# Sheet1.net
KiCad netlist of a schematic drawn in Altium Designer
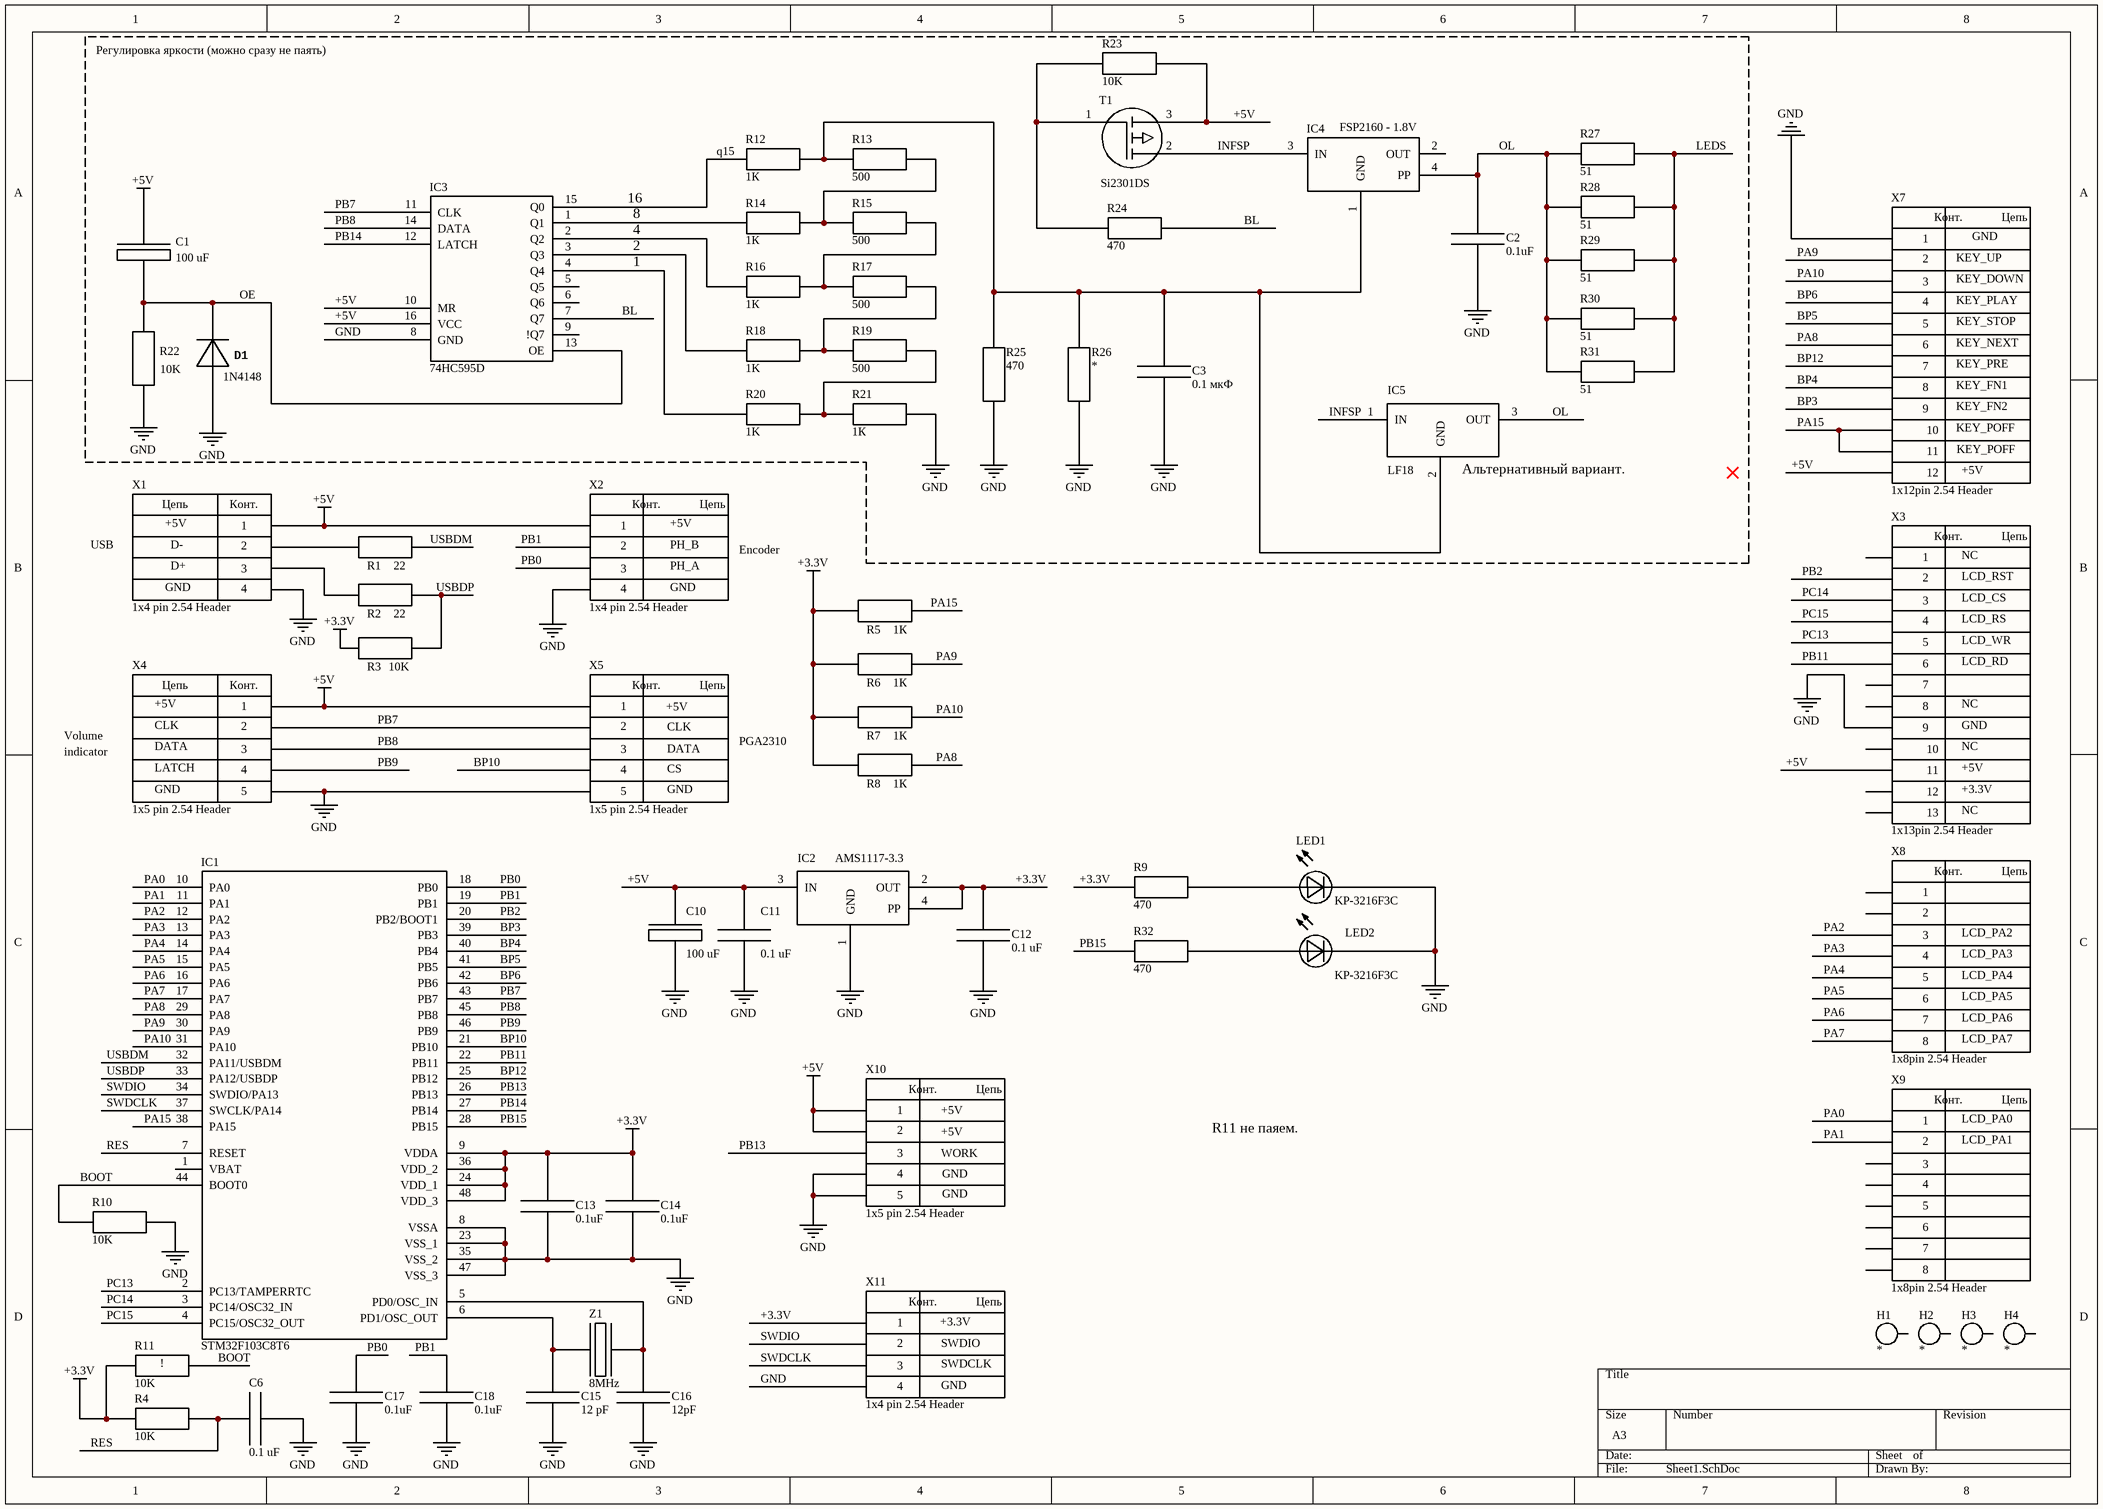
[diagram p0: Sheet1.SchDoc]

(export (version "E")
  (design (tool "Eeschema 10.0.6"))
  (components
    (comp (ref "C1")
      (value "100 uF")
      (footprint "Конденсатор тантал 4x7")
      (description "Танталовый")
      (libsource (lib "") (part "Конденсатор_1"))
    )
    (comp (ref "C2")
      (value "0.1uF")
      (footprint "SMD 1206 Конденсатор")
      (libsource (lib "S83") (part "Конденсатор"))
    )
    (comp (ref "C3")
      (value "0.1 мкФ")
      (footprint "SMD 1206 Конденсатор")
      (libsource (lib "S83") (part "Конденсатор"))
    )
    (comp (ref "C6")
      (value "0.1 uF")
      (footprint "SMD 1206 Конденсатор")
      (libsource (lib "S83") (part "Конденсатор"))
    )
    (comp (ref "C10")
      (value "100 uF")
      (footprint "Конденсатор тантал 4x7")
      (description "Танталовый")
      (libsource (lib "") (part "Конденсатор_1"))
    )
    (comp (ref "C11")
      (value "0.1 uF")
      (footprint "SMD 1206 Конденсатор")
      (description "Керамический")
      (libsource (lib "S83") (part "Конденсатор"))
    )
    (comp (ref "C12")
      (value "0.1 uF")
      (footprint "SMD 1206 Конденсатор")
      (description "Керамический")
      (libsource (lib "S83") (part "Конденсатор"))
    )
    (comp (ref "C13")
      (value "0.1uF")
      (footprint "SMD 1206 Конденсатор")
      (libsource (lib "S83") (part "Конденсатор"))
    )
    (comp (ref "C14")
      (value "0.1uF")
      (footprint "SMD 1206 Конденсатор")
      (libsource (lib "S83") (part "Конденсатор"))
    )
    (comp (ref "C15")
      (value "12 pF")
      (footprint "SMD 1206 Конденсатор")
      (libsource (lib "S83") (part "Конденсатор"))
    )
    (comp (ref "C16")
      (value "12pF")
      (footprint "SMD 1206 Конденсатор")
      (libsource (lib "S83") (part "Конденсатор"))
    )
    (comp (ref "C17")
      (value "0.1uF")
      (footprint "SMD 1206 Конденсатор")
      (libsource (lib "S83") (part "Конденсатор"))
    )
    (comp (ref "C18")
      (value "0.1uF")
      (footprint "SMD 1206 Конденсатор")
      (libsource (lib "S83") (part "Конденсатор"))
    )
    (comp (ref "D1") (value "1N4148") (footprint "SMD 1206 Диод") (libsource (lib "S83") (part "Диод")))
    (comp (ref "H1")
      (value "*")
      (footprint "Отверстие 3,2")
      (libsource (lib "S83") (part "Отверстие монтажное"))
    )
    (comp (ref "H2")
      (value "*")
      (footprint "Отверстие 3,2")
      (libsource (lib "S83") (part "Отверстие монтажное"))
    )
    (comp (ref "H3")
      (value "*")
      (footprint "Отверстие 3,2")
      (libsource (lib "S83") (part "Отверстие монтажное"))
    )
    (comp (ref "H4")
      (value "*")
      (footprint "Отверстие 3,2")
      (libsource (lib "S83") (part "Отверстие монтажное"))
    )
    (comp (ref "IC1")
      (value "STM32F103C8T6")
      (footprint "STM32F103C8T6")
      (description "Микроконтроллер")
      (libsource (lib "S83_IC") (part "STM32F103C8T6"))
    )
    (comp (ref "IC2")
      (value "AMS1117-3.3")
      (footprint "SOT-223")
      (description "Стабилизатор")
      (libsource (lib "S83_IC") (part "AMS1117"))
    )
    (comp (ref "IC3") (value "74HC595D") (footprint "SO-16") (libsource (lib "S83_IC") (part "74HC595D")))
    (comp (ref "IC4")
      (value "FSP2160 - 1.8V")
      (footprint "SOT-223")
      (libsource (lib "S83_IC") (part "FSP2160B J1003H1"))
    )
    (comp (ref "IC5") (value "LF18") (footprint "TO-252") (libsource (lib "S83_IC") (part "LF18")))
    (comp (ref "LED1")
      (value "KP-3216F3C")
      (footprint "SMD 1206 Светодиод ВАЙТ")
      (libsource (lib "S83") (part "Светодиод"))
    )
    (comp (ref "LED2")
      (value "KP-3216F3C")
      (footprint "SMD 1206 Светодиод ВАЙТ")
      (libsource (lib "S83") (part "Светодиод"))
    )
    (comp (ref "R1") (value "22") (footprint "SMD 1206 Резистор") (libsource (lib "S83") (part "Резистор")))
    (comp (ref "R2") (value "22") (footprint "SMD 1206 Резистор") (libsource (lib "S83") (part "Резистор")))
    (comp (ref "R3") (value "10K") (footprint "SMD 1206 Резистор") (libsource (lib "S83") (part "Резистор")))
    (comp (ref "R4") (value "10K") (footprint "SMD 1206 Резистор") (libsource (lib "S83") (part "Резистор")))
    (comp (ref "R5") (value "1К") (footprint "SMD 1206 Резистор") (libsource (lib "S83") (part "Резистор")))
    (comp (ref "R6") (value "1К") (footprint "SMD 1206 Резистор") (libsource (lib "S83") (part "Резистор")))
    (comp (ref "R7") (value "1К") (footprint "SMD 1206 Резистор") (libsource (lib "S83") (part "Резистор")))
    (comp (ref "R8") (value "1К") (footprint "SMD 1206 Резистор") (libsource (lib "S83") (part "Резистор")))
    (comp (ref "R9") (value "470") (footprint "SMD 1206 Резистор") (libsource (lib "S83") (part "Резистор")))
    (comp (ref "R10") (value "10K") (footprint "SMD 1206 Резистор") (libsource (lib "S83") (part "Резистор")))
    (comp (ref "R11") (value "10K") (footprint "SMD 1206 Резистор") (libsource (lib "S83") (part "Резистор")))
    (comp (ref "R12") (value "1К") (footprint "SMD 1206 Резистор") (libsource (lib "S83") (part "Резистор")))
    (comp (ref "R13") (value "500") (footprint "SMD 1206 Резистор") (libsource (lib "S83") (part "Резистор")))
    (comp (ref "R14") (value "1К") (footprint "SMD 1206 Резистор") (libsource (lib "S83") (part "Резистор")))
    (comp (ref "R15") (value "500") (footprint "SMD 1206 Резистор") (libsource (lib "S83") (part "Резистор")))
    (comp (ref "R16") (value "1К") (footprint "SMD 1206 Резистор") (libsource (lib "S83") (part "Резистор")))
    (comp (ref "R17") (value "500") (footprint "SMD 1206 Резистор") (libsource (lib "S83") (part "Резистор")))
    (comp (ref "R18") (value "1K") (footprint "SMD 1206 Резистор") (libsource (lib "S83") (part "Резистор")))
    (comp (ref "R19") (value "500") (footprint "SMD 1206 Резистор") (libsource (lib "S83") (part "Резистор")))
    (comp (ref "R20") (value "1K") (footprint "SMD 1206 Резистор") (libsource (lib "S83") (part "Резистор")))
    (comp (ref "R21") (value "1К") (footprint "SMD 1206 Резистор") (libsource (lib "S83") (part "Резистор")))
    (comp (ref "R22") (value "10K") (footprint "SMD 1206 Резистор") (libsource (lib "S83") (part "Резистор")))
    (comp (ref "R23") (value "10K") (footprint "SMD 1206 Резистор") (libsource (lib "S83") (part "Резистор")))
    (comp (ref "R24") (value "470") (footprint "SMD 1206 Резистор") (libsource (lib "S83") (part "Резистор")))
    (comp (ref "R25") (value "470") (footprint "SMD 1206 Резистор") (libsource (lib "S83") (part "Резистор")))
    (comp (ref "R26") (value "*") (footprint "SMD 1206 Резистор") (libsource (lib "S83") (part "Резистор")))
    (comp (ref "R27") (value "51") (footprint "SMD 1206 Резистор") (libsource (lib "S83") (part "Резистор")))
    (comp (ref "R28") (value "51") (footprint "SMD 1206 Резистор") (libsource (lib "S83") (part "Резистор")))
    (comp (ref "R29") (value "51") (footprint "SMD 1206 Резистор") (libsource (lib "S83") (part "Резистор")))
    (comp (ref "R30") (value "51") (footprint "SMD 1206 Резистор") (libsource (lib "S83") (part "Резистор")))
    (comp (ref "R31") (value "51") (footprint "SMD 1206 Резистор") (libsource (lib "S83") (part "Резистор")))
    (comp (ref "R32") (value "470") (footprint "SMD 1206 Резистор") (libsource (lib "S83") (part "Резистор")))
    (comp (ref "T1")
      (value "Si2301DS")
      (footprint "SMD SOT-23 Транзистор 3 pin")
      (libsource (lib "S83") (part "Транзистор MOSFET P-конал (как p-n-p)"))
    )
    (comp (ref "X1")
      (value "1x4 pin 2.54 Header")
      (footprint "(1x4)PIN 2.54 HEADR")
      (libsource (lib "S83_connectors") (part "(1x4)pin 2.54 Header"))
    )
    (comp (ref "X2")
      (value "1x4 pin 2.54 Header")
      (footprint "(1x4)PIN 2.54 HEADR")
      (libsource (lib "S83_connectors") (part "(1x4)pin 2.54 Header"))
    )
    (comp (ref "X3")
      (value "1x13pin 2.54 Header")
      (footprint "(1x13)pin 2.54 header")
      (description "к LCD")
      (libsource (lib "S83_connectors") (part "1x13pin 2.54 Header"))
    )
    (comp (ref "X4")
      (value "1x5 pin 2.54 Header")
      (footprint "(1x5)pin 2.54 Header")
      (libsource (lib "S83_connectors") (part "1x5pin 2.54 Header"))
    )
    (comp (ref "X5")
      (value "1x5 pin 2.54 Header")
      (footprint "(1x5)pin 2.54 Header")
      (libsource (lib "S83_connectors") (part "1x5pin 2.54 Header"))
    )
    (comp (ref "X7")
      (value "1x12pin 2.54 Header")
      (footprint "(1x12)pin 2.54 header")
      (description "Кнопки")
      (libsource (lib "S83_connectors") (part "1x12pin 2.54 Header"))
    )
    (comp (ref "X8")
      (value "1x8pin 2.54 Header")
      (footprint "(1x8)PIN 2.54 HEADER")
      (description "к LCD")
      (libsource (lib "S83_connectors") (part "1x8pin 2.54 Header"))
    )
    (comp (ref "X9")
      (value "1x8pin 2.54 Header")
      (footprint "(1x8)PIN 2.54 HEADER")
      (description "к LCD")
      (libsource (lib "S83_connectors") (part "1x8pin 2.54 Header"))
    )
    (comp (ref "X10")
      (value "1x5 pin 2.54 Header")
      (footprint "(1x5)pin 2.54 Header")
      (description "Папа")
      (libsource (lib "S83_connectors") (part "1x5pin 2.54 Header"))
    )
    (comp (ref "X11")
      (value "1x4 pin 2.54 Header")
      (footprint "(1x4)PIN 2.54 HEADR")
      (libsource (lib "S83_connectors") (part "(1x4)pin 2.54 Header"))
    )
    (comp (ref "Z1")
      (value "8MHz")
      (footprint "Кварцевый резонатор")
      (libsource (lib "S83") (part "Кварцевый резонатор"))
    )
  )
  (nets
    (net (code "1") (name "+3.3V") (class "Default")
      (node (ref "C12") (pin "1") (pinfunction "+_1") (pintype "passive"))
      (node (ref "C13") (pin "1") (pinfunction "+_1") (pintype "passive"))
      (node (ref "C14") (pin "1") (pinfunction "+_1") (pintype "passive"))
      (node (ref "IC1") (pin "24") (pinfunction "VDD_1_24") (pintype "passive"))
      (node (ref "IC1") (pin "36") (pinfunction "VDD_2_36") (pintype "passive"))
      (node (ref "IC1") (pin "48") (pinfunction "VDD_3_48") (pintype "passive"))
      (node (ref "IC1") (pin "9") (pinfunction "VDDA_9") (pintype "passive"))
      (node (ref "IC2") (pin "2") (pinfunction "OUT_2") (pintype "passive"))
      (node (ref "IC2") (pin "4") (pinfunction "PP_4") (pintype "passive"))
      (node (ref "R11") (pin "1") (pinfunction "left_1") (pintype "passive"))
      (node (ref "R3") (pin "1") (pinfunction "left_1") (pintype "passive"))
      (node (ref "R4") (pin "1") (pinfunction "left_1") (pintype "passive"))
      (node (ref "R5") (pin "1") (pinfunction "left_1") (pintype "passive"))
      (node (ref "R6") (pin "1") (pinfunction "left_1") (pintype "passive"))
      (node (ref "R7") (pin "1") (pinfunction "left_1") (pintype "passive"))
      (node (ref "R8") (pin "1") (pinfunction "left_1") (pintype "passive"))
      (node (ref "R9") (pin "1") (pinfunction "left_1") (pintype "passive"))
      (node (ref "X11") (pin "1") (pinfunction "1_1") (pintype "passive"))
    )
    (net (code "2") (name "+5V") (class "Default")
      (node (ref "C1") (pin "1") (pintype "passive"))
      (node (ref "C10") (pin "1") (pintype "passive"))
      (node (ref "C11") (pin "1") (pinfunction "+_1") (pintype "passive"))
      (node (ref "IC2") (pin "3") (pinfunction "IN_3") (pintype "passive"))
      (node (ref "IC3") (pin "10") (pinfunction "MR_10") (pintype "passive"))
      (node (ref "IC3") (pin "16") (pinfunction "VCC_16") (pintype "passive"))
      (node (ref "R23") (pin "2") (pinfunction "right_2") (pintype "passive"))
      (node (ref "T1") (pin "3") (pinfunction "3_3") (pintype "passive"))
      (node (ref "X1") (pin "1") (pinfunction "1_1") (pintype "passive"))
      (node (ref "X10") (pin "1") (pinfunction "1_1") (pintype "passive"))
      (node (ref "X10") (pin "2") (pinfunction "2_2") (pintype "passive"))
      (node (ref "X2") (pin "1") (pinfunction "1_1") (pintype "passive"))
      (node (ref "X3") (pin "11") (pinfunction "11_11") (pintype "passive"))
      (node (ref "X4") (pin "1") (pinfunction "1_1") (pintype "passive"))
      (node (ref "X5") (pin "1") (pinfunction "1_1") (pintype "passive"))
      (node (ref "X7") (pin "12") (pinfunction "12_12") (pintype "passive"))
    )
    (net (code "3") (name "/BL") (class "Default")
      (node (ref "IC3") (pin "7") (pinfunction "Q7_7") (pintype "passive"))
      (node (ref "R24") (pin "2") (pinfunction "right_2") (pintype "passive"))
    )
    (net (code "4") (name "/BOOT") (class "Default")
      (node (ref "IC1") (pin "44") (pinfunction "BOOT0_44") (pintype "passive"))
      (node (ref "R10") (pin "1") (pinfunction "left_1") (pintype "passive"))
      (node (ref "R11") (pin "2") (pinfunction "right_2") (pintype "passive"))
    )
    (net (code "5") (name "/BP3") (class "Default")
      (node (ref "IC1") (pin "39") (pinfunction "PB3_39") (pintype "passive"))
      (node (ref "X7") (pin "9") (pinfunction "9_9") (pintype "passive"))
    )
    (net (code "6") (name "/BP4") (class "Default")
      (node (ref "IC1") (pin "40") (pinfunction "PB4_40") (pintype "passive"))
      (node (ref "X7") (pin "8") (pinfunction "8_8") (pintype "passive"))
    )
    (net (code "7") (name "/BP5") (class "Default")
      (node (ref "IC1") (pin "41") (pinfunction "PB5_41") (pintype "passive"))
      (node (ref "X7") (pin "5") (pinfunction "5_5") (pintype "passive"))
    )
    (net (code "8") (name "/BP6") (class "Default")
      (node (ref "IC1") (pin "42") (pinfunction "PB6_42") (pintype "passive"))
      (node (ref "X7") (pin "4") (pinfunction "4_4") (pintype "passive"))
    )
    (net (code "9") (name "/BP10") (class "Default")
      (node (ref "IC1") (pin "21") (pinfunction "PB10_21") (pintype "passive"))
      (node (ref "X5") (pin "4") (pinfunction "4_4") (pintype "passive"))
    )
    (net (code "10") (name "/BP12") (class "Default")
      (node (ref "IC1") (pin "25") (pinfunction "PB12_25") (pintype "passive"))
      (node (ref "X7") (pin "7") (pinfunction "7_7") (pintype "passive"))
    )
    (net (code "11") (name "/INFSP") (class "Default")
      (node (ref "IC4") (pin "3") (pinfunction "IN_3") (pintype "passive"))
      (node (ref "IC5") (pin "1") (pinfunction "IN_1") (pintype "passive"))
      (node (ref "T1") (pin "2") (pinfunction "2_2") (pintype "passive"))
    )
    (net (code "12") (name "/LEDS") (class "Default")
      (node (ref "R27") (pin "2") (pinfunction "right_2") (pintype "passive"))
      (node (ref "R28") (pin "2") (pinfunction "right_2") (pintype "passive"))
      (node (ref "R29") (pin "2") (pinfunction "right_2") (pintype "passive"))
      (node (ref "R30") (pin "2") (pinfunction "right_2") (pintype "passive"))
      (node (ref "R31") (pin "2") (pinfunction "right_2") (pintype "passive"))
    )
    (net (code "13") (name "/OE") (class "Default")
      (node (ref "C1") (pin "2") (pinfunction "2_2") (pintype "passive"))
      (node (ref "D1") (pin "2") (pinfunction "K_2") (pintype "passive"))
      (node (ref "IC3") (pin "13") (pinfunction "OE_13") (pintype "passive"))
      (node (ref "R22") (pin "1") (pinfunction "left_1") (pintype "passive"))
    )
    (net (code "14") (name "/OL") (class "Default")
      (node (ref "C2") (pin "1") (pinfunction "+_1") (pintype "passive"))
      (node (ref "IC4") (pin "4") (pinfunction "PP_4") (pintype "passive"))
      (node (ref "IC5") (pin "3") (pinfunction "OUT_3") (pintype "passive"))
      (node (ref "R27") (pin "1") (pinfunction "left_1") (pintype "passive"))
      (node (ref "R28") (pin "1") (pinfunction "left_1") (pintype "passive"))
      (node (ref "R29") (pin "1") (pinfunction "left_1") (pintype "passive"))
      (node (ref "R30") (pin "1") (pinfunction "left_1") (pintype "passive"))
      (node (ref "R31") (pin "1") (pinfunction "left_1") (pintype "passive"))
    )
    (net (code "15") (name "/PA0") (class "Default")
      (node (ref "IC1") (pin "10") (pinfunction "PA0_10") (pintype "passive"))
      (node (ref "X9") (pin "1") (pinfunction "1_1") (pintype "passive"))
    )
    (net (code "16") (name "/PA1") (class "Default")
      (node (ref "IC1") (pin "11") (pinfunction "PA1_11") (pintype "passive"))
      (node (ref "X9") (pin "2") (pinfunction "2_2") (pintype "passive"))
    )
    (net (code "17") (name "/PA2") (class "Default")
      (node (ref "IC1") (pin "12") (pinfunction "PA2_12") (pintype "passive"))
      (node (ref "X8") (pin "3") (pinfunction "3_3") (pintype "passive"))
    )
    (net (code "18") (name "/PA3") (class "Default")
      (node (ref "IC1") (pin "13") (pinfunction "PA3_13") (pintype "passive"))
      (node (ref "X8") (pin "4") (pinfunction "4_4") (pintype "passive"))
    )
    (net (code "19") (name "/PA4") (class "Default")
      (node (ref "IC1") (pin "14") (pinfunction "PA4_14") (pintype "passive"))
      (node (ref "X8") (pin "5") (pinfunction "5_5") (pintype "passive"))
    )
    (net (code "20") (name "/PA5") (class "Default")
      (node (ref "IC1") (pin "15") (pinfunction "PA5_15") (pintype "passive"))
      (node (ref "X8") (pin "6") (pinfunction "6_6") (pintype "passive"))
    )
    (net (code "21") (name "/PA6") (class "Default")
      (node (ref "IC1") (pin "16") (pinfunction "PA6_16") (pintype "passive"))
      (node (ref "X8") (pin "7") (pinfunction "7_7") (pintype "passive"))
    )
    (net (code "22") (name "/PA7") (class "Default")
      (node (ref "IC1") (pin "17") (pinfunction "PA7_17") (pintype "passive"))
      (node (ref "X8") (pin "8") (pinfunction "8_8") (pintype "passive"))
    )
    (net (code "23") (name "/PA8") (class "Default")
      (node (ref "IC1") (pin "29") (pinfunction "PA8_29") (pintype "passive"))
      (node (ref "R8") (pin "2") (pinfunction "right_2") (pintype "passive"))
      (node (ref "X7") (pin "6") (pinfunction "6_6") (pintype "passive"))
    )
    (net (code "24") (name "/PA9") (class "Default")
      (node (ref "IC1") (pin "30") (pinfunction "PA9_30") (pintype "passive"))
      (node (ref "R6") (pin "2") (pinfunction "right_2") (pintype "passive"))
      (node (ref "X7") (pin "2") (pinfunction "2_2") (pintype "passive"))
    )
    (net (code "25") (name "/PA10") (class "Default")
      (node (ref "IC1") (pin "31") (pinfunction "PA10_31") (pintype "passive"))
      (node (ref "R7") (pin "2") (pinfunction "right_2") (pintype "passive"))
      (node (ref "X7") (pin "3") (pinfunction "3_3") (pintype "passive"))
    )
    (net (code "26") (name "/PA15") (class "Default")
      (node (ref "IC1") (pin "38") (pinfunction "PA15_38") (pintype "passive"))
      (node (ref "R5") (pin "2") (pinfunction "right_2") (pintype "passive"))
      (node (ref "X7") (pin "10") (pinfunction "10_10") (pintype "passive"))
      (node (ref "X7") (pin "11") (pinfunction "11_11") (pintype "passive"))
    )
    (net (code "27") (name "/PB0") (class "Default")
      (node (ref "C17") (pin "1") (pinfunction "+_1") (pintype "passive"))
      (node (ref "IC1") (pin "18") (pinfunction "PB0_18") (pintype "passive"))
      (node (ref "X2") (pin "3") (pinfunction "3_3") (pintype "passive"))
    )
    (net (code "28") (name "/PB1") (class "Default")
      (node (ref "C18") (pin "1") (pinfunction "+_1") (pintype "passive"))
      (node (ref "IC1") (pin "19") (pinfunction "PB1_19") (pintype "passive"))
      (node (ref "X2") (pin "2") (pinfunction "2_2") (pintype "passive"))
    )
    (net (code "29") (name "/PB2") (class "Default")
      (node (ref "IC1") (pin "20") (pinfunction "PB2/BOOT1_20") (pintype "passive"))
      (node (ref "X3") (pin "2") (pinfunction "2_2") (pintype "passive"))
    )
    (net (code "30") (name "/PB7") (class "Default")
      (node (ref "IC1") (pin "43") (pinfunction "PB7_43") (pintype "passive"))
      (node (ref "IC3") (pin "11") (pinfunction "CLK_11") (pintype "passive"))
      (node (ref "X4") (pin "2") (pinfunction "2_2") (pintype "passive"))
      (node (ref "X5") (pin "2") (pinfunction "2_2") (pintype "passive"))
    )
    (net (code "31") (name "/PB8") (class "Default")
      (node (ref "IC1") (pin "45") (pinfunction "PB8_45") (pintype "passive"))
      (node (ref "IC3") (pin "14") (pinfunction "DATA_14") (pintype "passive"))
      (node (ref "X4") (pin "3") (pinfunction "3_3") (pintype "passive"))
      (node (ref "X5") (pin "3") (pinfunction "3_3") (pintype "passive"))
    )
    (net (code "32") (name "/PB9") (class "Default")
      (node (ref "IC1") (pin "46") (pinfunction "PB9_46") (pintype "passive"))
      (node (ref "X4") (pin "4") (pinfunction "4_4") (pintype "passive"))
    )
    (net (code "33") (name "/PB11") (class "Default")
      (node (ref "IC1") (pin "22") (pinfunction "PB11_22") (pintype "passive"))
      (node (ref "X3") (pin "6") (pinfunction "6_6") (pintype "passive"))
    )
    (net (code "34") (name "/PB13") (class "Default")
      (node (ref "IC1") (pin "26") (pinfunction "PB13_26") (pintype "passive"))
      (node (ref "X10") (pin "3") (pinfunction "3_3") (pintype "passive"))
    )
    (net (code "35") (name "/PB14") (class "Default")
      (node (ref "IC1") (pin "27") (pinfunction "PB14_27") (pintype "passive"))
      (node (ref "IC3") (pin "12") (pinfunction "LATCH_12") (pintype "passive"))
    )
    (net (code "36") (name "/PB15") (class "Default")
      (node (ref "IC1") (pin "28") (pinfunction "PB15_28") (pintype "passive"))
      (node (ref "R32") (pin "2") (pinfunction "right_2") (pintype "passive"))
    )
    (net (code "37") (name "/PC13") (class "Default")
      (node (ref "IC1") (pin "2") (pinfunction "PC13/TAMPERRTC_2") (pintype "passive"))
      (node (ref "X3") (pin "5") (pinfunction "5_5") (pintype "passive"))
    )
    (net (code "38") (name "/PC14") (class "Default")
      (node (ref "IC1") (pin "3") (pinfunction "PC14/OSC32_IN_3") (pintype "passive"))
      (node (ref "X3") (pin "3") (pinfunction "3_3") (pintype "passive"))
    )
    (net (code "39") (name "/PC15") (class "Default")
      (node (ref "IC1") (pin "4") (pinfunction "PC15/OSC32_OUT_4") (pintype "passive"))
      (node (ref "X3") (pin "4") (pinfunction "4_4") (pintype "passive"))
    )
    (net (code "40") (name "/RES") (class "Default")
      (node (ref "C6") (pin "1") (pinfunction "+_1") (pintype "passive"))
      (node (ref "IC1") (pin "7") (pinfunction "RESET_7") (pintype "passive"))
      (node (ref "R4") (pin "2") (pinfunction "right_2") (pintype "passive"))
    )
    (net (code "41") (name "/SWDCLK") (class "Default")
      (node (ref "IC1") (pin "37") (pinfunction "SWCLK/PA14_37") (pintype "passive"))
      (node (ref "X11") (pin "3") (pinfunction "3_3") (pintype "passive"))
    )
    (net (code "42") (name "/SWDIO") (class "Default")
      (node (ref "IC1") (pin "34") (pinfunction "SWDIO/PA13_34") (pintype "passive"))
      (node (ref "X11") (pin "2") (pinfunction "2_2") (pintype "passive"))
    )
    (net (code "43") (name "/USBDM") (class "Default")
      (node (ref "IC1") (pin "32") (pinfunction "PA11/USBDM_32") (pintype "passive"))
      (node (ref "R1") (pin "2") (pinfunction "right_2") (pintype "passive"))
    )
    (net (code "44") (name "/USBDP") (class "Default")
      (node (ref "IC1") (pin "33") (pinfunction "PA12/USBDP_33") (pintype "passive"))
      (node (ref "R2") (pin "2") (pinfunction "right_2") (pintype "passive"))
      (node (ref "R3") (pin "2") (pinfunction "right_2") (pintype "passive"))
    )
    (net (code "45") (name "/q15") (class "Default")
      (node (ref "IC3") (pin "15") (pinfunction "Q0_15") (pintype "passive"))
      (node (ref "R12") (pin "1") (pinfunction "left_1") (pintype "passive"))
    )
    (net (code "46") (name "GND") (class "Default")
      (node (ref "C10") (pin "2") (pinfunction "2_2") (pintype "passive"))
      (node (ref "C11") (pin "2") (pinfunction "-_2") (pintype "passive"))
      (node (ref "C12") (pin "2") (pinfunction "-_2") (pintype "passive"))
      (node (ref "C13") (pin "2") (pinfunction "-_2") (pintype "passive"))
      (node (ref "C14") (pin "2") (pinfunction "-_2") (pintype "passive"))
      (node (ref "C15") (pin "2") (pinfunction "-_2") (pintype "passive"))
      (node (ref "C16") (pin "2") (pinfunction "-_2") (pintype "passive"))
      (node (ref "C17") (pin "2") (pinfunction "-_2") (pintype "passive"))
      (node (ref "C18") (pin "2") (pinfunction "-_2") (pintype "passive"))
      (node (ref "C2") (pin "2") (pinfunction "-_2") (pintype "passive"))
      (node (ref "C3") (pin "2") (pinfunction "-_2") (pintype "passive"))
      (node (ref "C6") (pin "2") (pinfunction "-_2") (pintype "passive"))
      (node (ref "D1") (pin "1") (pinfunction "А_1") (pintype "passive"))
      (node (ref "IC1") (pin "23") (pinfunction "VSS_1_23") (pintype "passive"))
      (node (ref "IC1") (pin "35") (pinfunction "VSS_2_35") (pintype "passive"))
      (node (ref "IC1") (pin "47") (pinfunction "VSS_3_47") (pintype "passive"))
      (node (ref "IC1") (pin "8") (pinfunction "VSSA_8") (pintype "passive"))
      (node (ref "IC2") (pin "1") (pinfunction "GND_1") (pintype "passive"))
      (node (ref "IC3") (pin "8") (pinfunction "GND_8") (pintype "passive"))
      (node (ref "LED1") (pin "2") (pinfunction "K_2") (pintype "passive"))
      (node (ref "LED2") (pin "2") (pinfunction "K_2") (pintype "passive"))
      (node (ref "R10") (pin "2") (pinfunction "right_2") (pintype "passive"))
      (node (ref "R21") (pin "2") (pinfunction "right_2") (pintype "passive"))
      (node (ref "R22") (pin "2") (pinfunction "right_2") (pintype "passive"))
      (node (ref "R25") (pin "1") (pinfunction "left_1") (pintype "passive"))
      (node (ref "R26") (pin "2") (pinfunction "right_2") (pintype "passive"))
      (node (ref "X1") (pin "4") (pinfunction "4_4") (pintype "passive"))
      (node (ref "X10") (pin "4") (pinfunction "4_4") (pintype "passive"))
      (node (ref "X10") (pin "5") (pinfunction "5_5") (pintype "passive"))
      (node (ref "X11") (pin "4") (pinfunction "4_4") (pintype "passive"))
      (node (ref "X2") (pin "4") (pinfunction "4_4") (pintype "passive"))
      (node (ref "X3") (pin "9") (pinfunction "9_9") (pintype "passive"))
      (node (ref "X4") (pin "5") (pinfunction "5_5") (pintype "passive"))
      (node (ref "X5") (pin "5") (pinfunction "5_5") (pintype "passive"))
      (node (ref "X7") (pin "1") (pinfunction "1_1") (pintype "passive"))
    )
    (net (code "47") (name "Net-(C3-+)") (class "Default")
      (node (ref "C3") (pin "1") (pinfunction "+_1") (pintype "passive"))
      (node (ref "IC4") (pin "1") (pinfunction "GND_1") (pintype "passive"))
      (node (ref "IC5") (pin "2") (pinfunction "GND_2") (pintype "passive"))
      (node (ref "R12") (pin "2") (pinfunction "right_2") (pintype "passive"))
      (node (ref "R13") (pin "1") (pinfunction "left_1") (pintype "passive"))
      (node (ref "R25") (pin "2") (pinfunction "right_2") (pintype "passive"))
      (node (ref "R26") (pin "1") (pinfunction "left_1") (pintype "passive"))
    )
    (net (code "48") (name "Net-(C15-+)") (class "Default")
      (node (ref "C15") (pin "1") (pinfunction "+_1") (pintype "passive"))
      (node (ref "IC1") (pin "6") (pinfunction "PD1/OSC_OUT_6") (pintype "passive"))
      (node (ref "Z1") (pin "1") (pinfunction "1_1") (pintype "passive"))
    )
    (net (code "49") (name "Net-(C16-+)") (class "Default")
      (node (ref "C16") (pin "1") (pinfunction "+_1") (pintype "passive"))
      (node (ref "IC1") (pin "5") (pinfunction "PD0/OSC_IN_5") (pintype "passive"))
      (node (ref "Z1") (pin "2") (pinfunction "2_2") (pintype "passive"))
    )
    (net (code "50") (name "Net-(IC3-Q1)") (class "Default")
      (node (ref "IC3") (pin "1") (pinfunction "Q1_1") (pintype "passive"))
      (node (ref "R14") (pin "1") (pinfunction "left_1") (pintype "passive"))
    )
    (net (code "51") (name "Net-(IC3-Q2)") (class "Default")
      (node (ref "IC3") (pin "2") (pinfunction "Q2_2") (pintype "passive"))
      (node (ref "R16") (pin "1") (pinfunction "left_1") (pintype "passive"))
    )
    (net (code "52") (name "Net-(IC3-Q3)") (class "Default")
      (node (ref "IC3") (pin "3") (pinfunction "Q3_3") (pintype "passive"))
      (node (ref "R18") (pin "1") (pinfunction "left_1") (pintype "passive"))
    )
    (net (code "53") (name "Net-(IC3-Q4)") (class "Default")
      (node (ref "IC3") (pin "4") (pinfunction "Q4_4") (pintype "passive"))
      (node (ref "R20") (pin "1") (pinfunction "left_1") (pintype "passive"))
    )
    (net (code "54") (name "Net-(LED1-А)") (class "Default")
      (node (ref "LED1") (pin "1") (pinfunction "А_1") (pintype "passive"))
      (node (ref "R9") (pin "2") (pinfunction "right_2") (pintype "passive"))
    )
    (net (code "55") (name "Net-(LED2-А)") (class "Default")
      (node (ref "LED2") (pin "1") (pinfunction "А_1") (pintype "passive"))
      (node (ref "R32") (pin "1") (pinfunction "left_1") (pintype "passive"))
    )
    (net (code "56") (name "Net-(R1-left)") (class "Default")
      (node (ref "R1") (pin "1") (pinfunction "left_1") (pintype "passive"))
      (node (ref "X1") (pin "2") (pinfunction "2_2") (pintype "passive"))
    )
    (net (code "57") (name "Net-(R2-left)") (class "Default")
      (node (ref "R2") (pin "1") (pinfunction "left_1") (pintype "passive"))
      (node (ref "X1") (pin "3") (pinfunction "3_3") (pintype "passive"))
    )
    (net (code "58") (name "Net-(R13-right)") (class "Default")
      (node (ref "R13") (pin "2") (pinfunction "right_2") (pintype "passive"))
      (node (ref "R14") (pin "2") (pinfunction "right_2") (pintype "passive"))
      (node (ref "R15") (pin "2") (pinfunction "right_2") (pintype "passive"))
    )
    (net (code "59") (name "Net-(R15-left)") (class "Default")
      (node (ref "R15") (pin "1") (pinfunction "left_1") (pintype "passive"))
      (node (ref "R16") (pin "2") (pinfunction "right_2") (pintype "passive"))
      (node (ref "R17") (pin "1") (pinfunction "left_1") (pintype "passive"))
    )
    (net (code "60") (name "Net-(R17-right)") (class "Default")
      (node (ref "R17") (pin "2") (pinfunction "right_2") (pintype "passive"))
      (node (ref "R18") (pin "2") (pinfunction "right_2") (pintype "passive"))
      (node (ref "R19") (pin "1") (pinfunction "left_1") (pintype "passive"))
    )
    (net (code "61") (name "Net-(R19-right)") (class "Default")
      (node (ref "R19") (pin "2") (pinfunction "right_2") (pintype "passive"))
      (node (ref "R20") (pin "2") (pinfunction "right_2") (pintype "passive"))
      (node (ref "R21") (pin "1") (pinfunction "left_1") (pintype "passive"))
    )
    (net (code "62") (name "Net-(R23-left)") (class "Default")
      (node (ref "R23") (pin "1") (pinfunction "left_1") (pintype "passive"))
      (node (ref "R24") (pin "1") (pinfunction "left_1") (pintype "passive"))
      (node (ref "T1") (pin "1") (pinfunction "1_1") (pintype "passive"))
    )
    (net (code "63") (name "unconnected-(H1-Pad1)") (class "Default")
      (node (ref "H1") (pin "1") (pinfunction "1_1") (pintype "passive"))
    )
    (net (code "64") (name "unconnected-(H2-Pad1)") (class "Default")
      (node (ref "H2") (pin "1") (pinfunction "1_1") (pintype "passive"))
    )
    (net (code "65") (name "unconnected-(H3-Pad1)") (class "Default")
      (node (ref "H3") (pin "1") (pinfunction "1_1") (pintype "passive"))
    )
    (net (code "66") (name "unconnected-(H4-Pad1)") (class "Default")
      (node (ref "H4") (pin "1") (pinfunction "1_1") (pintype "passive"))
    )
    (net (code "67") (name "unconnected-(IC1-VBAT-Pad1)") (class "Default")
      (node (ref "IC1") (pin "1") (pinfunction "VBAT_1") (pintype "passive"))
    )
    (net (code "68") (name "unconnected-(IC3-!Q7-Pad9)") (class "Default")
      (node (ref "IC3") (pin "9") (pinfunction "!Q7_9") (pintype "passive"))
    )
    (net (code "69") (name "unconnected-(IC3-Q5-Pad5)") (class "Default")
      (node (ref "IC3") (pin "5") (pinfunction "Q5_5") (pintype "passive"))
    )
    (net (code "70") (name "unconnected-(IC3-Q6-Pad6)") (class "Default")
      (node (ref "IC3") (pin "6") (pinfunction "Q6_6") (pintype "passive"))
    )
    (net (code "71") (name "unconnected-(IC4-OUT-Pad2)") (class "Default")
      (node (ref "IC4") (pin "2") (pinfunction "OUT_2") (pintype "passive"))
    )
    (net (code "72") (name "unconnected-(X3-Pad1)") (class "Default")
      (node (ref "X3") (pin "1") (pinfunction "1_1") (pintype "passive"))
    )
    (net (code "73") (name "unconnected-(X3-Pad7)") (class "Default")
      (node (ref "X3") (pin "7") (pinfunction "7_7") (pintype "passive"))
    )
    (net (code "74") (name "unconnected-(X3-Pad8)") (class "Default")
      (node (ref "X3") (pin "8") (pinfunction "8_8") (pintype "passive"))
    )
    (net (code "75") (name "unconnected-(X3-Pad10)") (class "Default")
      (node (ref "X3") (pin "10") (pinfunction "10_10") (pintype "passive"))
    )
    (net (code "76") (name "unconnected-(X3-Pad11)") (class "Default")
      (node (ref "X3") (pin "11") (pinfunction "11_11") (pintype "passive"))
    )
    (net (code "77") (name "unconnected-(X3-Pad11)_1") (class "Default")
      (node (ref "X3") (pin "11") (pinfunction "11_11") (pintype "passive"))
    )
    (net (code "78") (name "unconnected-(X8-Pad1)") (class "Default")
      (node (ref "X8") (pin "1") (pinfunction "1_1") (pintype "passive"))
    )
    (net (code "79") (name "unconnected-(X8-Pad2)") (class "Default")
      (node (ref "X8") (pin "2") (pinfunction "2_2") (pintype "passive"))
    )
    (net (code "80") (name "unconnected-(X9-Pad3)") (class "Default")
      (node (ref "X9") (pin "3") (pinfunction "3_3") (pintype "passive"))
    )
    (net (code "81") (name "unconnected-(X9-Pad4)") (class "Default")
      (node (ref "X9") (pin "4") (pinfunction "4_4") (pintype "passive"))
    )
    (net (code "82") (name "unconnected-(X9-Pad5)") (class "Default")
      (node (ref "X9") (pin "5") (pinfunction "5_5") (pintype "passive"))
    )
    (net (code "83") (name "unconnected-(X9-Pad6)") (class "Default")
      (node (ref "X9") (pin "6") (pinfunction "6_6") (pintype "passive"))
    )
    (net (code "84") (name "unconnected-(X9-Pad7)") (class "Default")
      (node (ref "X9") (pin "7") (pinfunction "7_7") (pintype "passive"))
    )
    (net (code "85") (name "unconnected-(X9-Pad8)") (class "Default")
      (node (ref "X9") (pin "8") (pinfunction "8_8") (pintype "passive"))
    )
  )
)
